# I2C_extender_1.net
KiCad netlist of a schematic drawn in Altium Designer
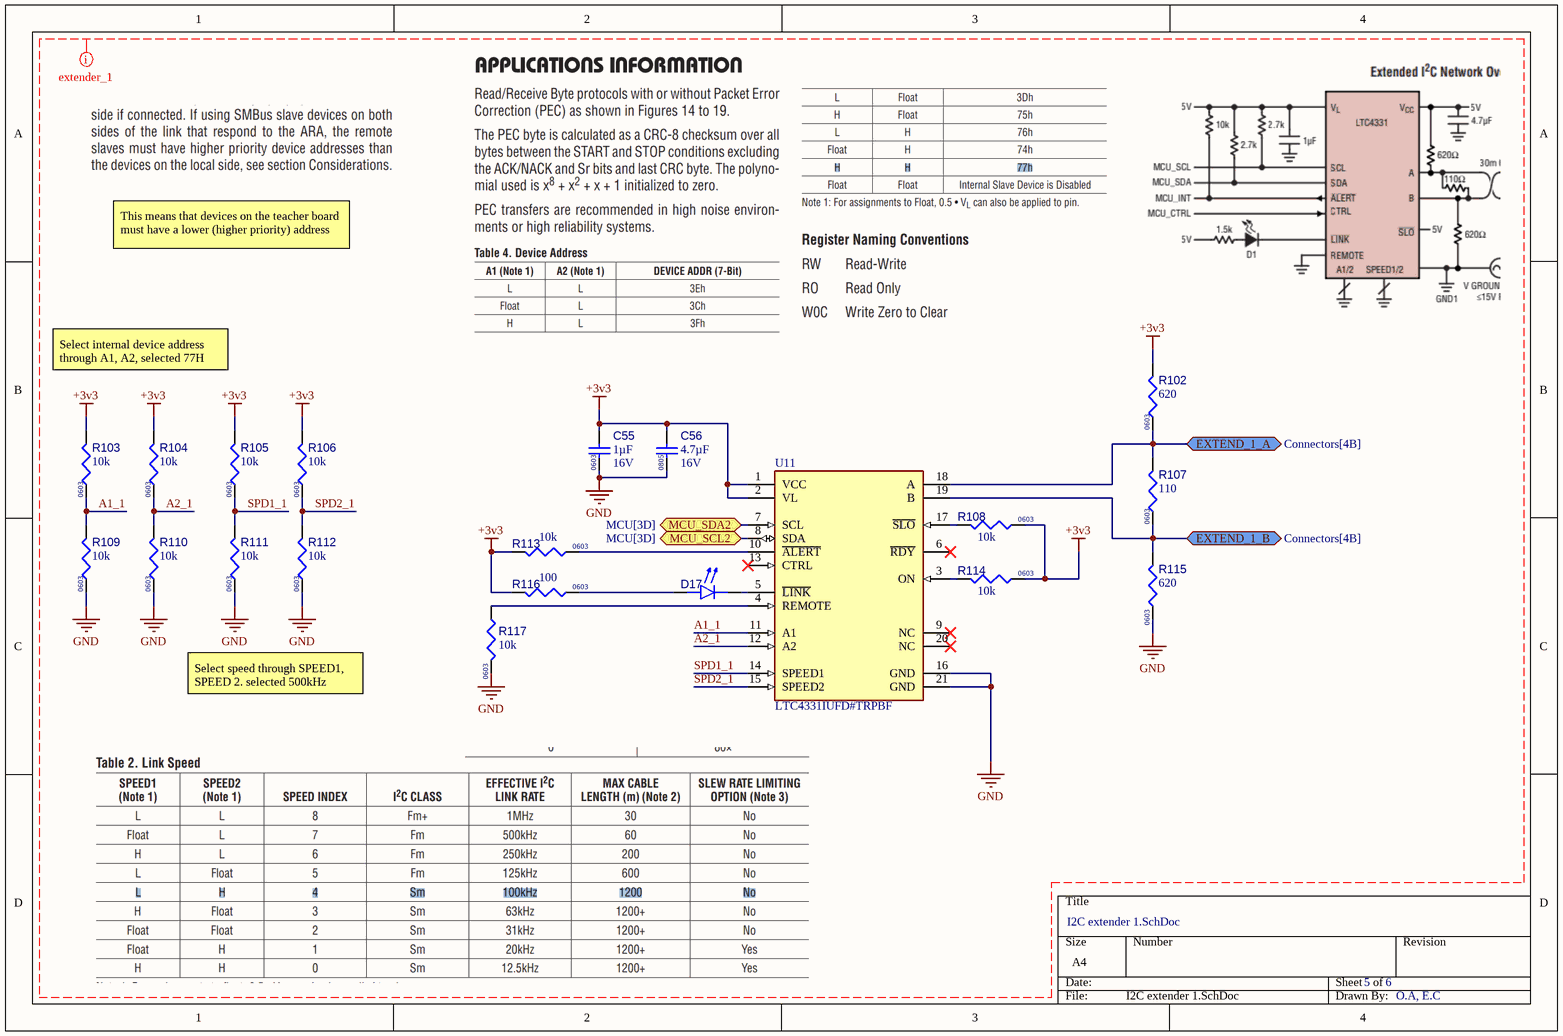
[diagram p0: I2C extender 1.SchDoc]

(export (version "E")
  (design (tool "Eeschema 10.0.6"))
  (components
    (comp (ref "C55")
      (value "1µF")
      (footprint "CAPC1608X90X35NL15T15")
      (description "Chip Capacitor, 1 uF, +/- 10%, 16 V, 0603 (1608 Metric)")
      (fields
        (field (name "CASE/PACKAGE") "0603")
        (field (name "VOLTAGE RATING") "16V")
        (field (name "TOLERANCE") "10%")
        (field (name "Comment") "Capacitor 1uF +/- 10% 16V 0603")
      )
      (libsource (lib "hawaiirobotics") (part "CAP-NP-2"))
    )
    (comp (ref "C56")
      (value "4.7µF")
      (footprint "CL21A475KOFNNNE-Footprint-1")
      (fields
        (field (name "CASE/PACKAGE") "0805")
        (field (name "RATED DC VOLTAGE (URDC)") "16V")
        (field (name "Comment") "CL21A475KOFNNNE")
      )
      (libsource (lib "hawaiirobotics") (part "CAP-NP-2"))
    )
    (comp (ref "D17")
      (value "150060YS75000")
      (footprint "WL-SMCW_0603_150060xx75000")
      (description "Single Color LED, Yellow, Water Clear, 1.1mm")
      (libsource (lib "hawaiirobotics") (part "DIODE-LED-2"))
    )
    (comp (ref "R102")
      (value "620")
      (footprint "RC0603JR-0720KL-Footprint-1")
      (fields
        (field (name "POWER") "100mW")
        (field (name "CASE/PACKAGE") "0603")
        (field (name "TOLERANCE") "1%")
        (field (name "Comment") "RC0603FR-07620RL")
      )
      (libsource (lib "hawaiirobotics") (part "RES-2"))
    )
    (comp (ref "R103")
      (value "10k")
      (footprint "RESC1608X55X25NL10T15")
      (description "Chip Resistor, 10 KOhm, +/- 1%, 01 W, -55 to 155 degC, 0603 (1608 Metric)")
      (fields
        (field (name "CASE/PACKAGE") "0603")
        (field (name "POWER") "100mW")
        (field (name "TOLERANCE") "1%")
      )
      (libsource (lib "hawaiirobotics") (part "RES-2"))
    )
    (comp (ref "R104")
      (value "10k")
      (footprint "RESC1608X55X25NL10T15")
      (description "Chip Resistor, 10 KOhm, +/- 1%, 01 W, -55 to 155 degC, 0603 (1608 Metric)")
      (fields
        (field (name "CASE/PACKAGE") "0603")
        (field (name "POWER") "100mW")
        (field (name "TOLERANCE") "1%")
      )
      (libsource (lib "hawaiirobotics") (part "RES-2"))
    )
    (comp (ref "R105")
      (value "10k")
      (footprint "RESC1608X55X25NL10T15")
      (description "Chip Resistor, 10 KOhm, +/- 1%, 01 W, -55 to 155 degC, 0603 (1608 Metric)")
      (fields
        (field (name "CASE/PACKAGE") "0603")
        (field (name "POWER") "100mW")
        (field (name "TOLERANCE") "1%")
      )
      (libsource (lib "hawaiirobotics") (part "RES-2"))
    )
    (comp (ref "R106")
      (value "10k")
      (footprint "RESC1608X55X25NL10T15")
      (description "Chip Resistor, 10 KOhm, +/- 1%, 01 W, -55 to 155 degC, 0603 (1608 Metric)")
      (fields
        (field (name "CASE/PACKAGE") "0603")
        (field (name "POWER") "100mW")
        (field (name "TOLERANCE") "1%")
      )
      (libsource (lib "hawaiirobotics") (part "RES-2"))
    )
    (comp (ref "R107")
      (value "110")
      (footprint "RC0603JR-0720KL-Footprint-1")
      (fields
        (field (name "TOLERANCE") "1%")
        (field (name "POWER") "100mW")
        (field (name "CASE/PACKAGE") "0603")
        (field (name "Comment") "RC0603FR-07110RL")
      )
      (libsource (lib "hawaiirobotics") (part "RES-2"))
    )
    (comp (ref "R108")
      (value "10k")
      (footprint "RESC1608X55X25NL10T15")
      (description "Chip Resistor, 10 KOhm, +/- 1%, 01 W, -55 to 155 degC, 0603 (1608 Metric)")
      (fields
        (field (name "CASE/PACKAGE") "0603")
        (field (name "POWER") "100mW")
        (field (name "TOLERANCE") "1%")
      )
      (libsource (lib "hawaiirobotics") (part "RES-2"))
    )
    (comp (ref "R109")
      (value "10k")
      (footprint "RESC1608X55X25NL10T15")
      (description "Chip Resistor, 10 KOhm, +/- 1%, 01 W, -55 to 155 degC, 0603 (1608 Metric)")
      (fields
        (field (name "CASE/PACKAGE") "0603")
        (field (name "POWER") "100mW")
        (field (name "TOLERANCE") "1%")
      )
      (libsource (lib "hawaiirobotics") (part "RES-2"))
    )
    (comp (ref "R110")
      (value "10k")
      (footprint "RESC1608X55X25NL10T15")
      (description "Chip Resistor, 10 KOhm, +/- 1%, 01 W, -55 to 155 degC, 0603 (1608 Metric)")
      (fields
        (field (name "CASE/PACKAGE") "0603")
        (field (name "POWER") "100mW")
        (field (name "TOLERANCE") "1%")
      )
      (libsource (lib "hawaiirobotics") (part "RES-2"))
    )
    (comp (ref "R111")
      (value "10k")
      (footprint "RESC1608X55X25NL10T15")
      (description "Chip Resistor, 10 KOhm, +/- 1%, 01 W, -55 to 155 degC, 0603 (1608 Metric)")
      (fields
        (field (name "CASE/PACKAGE") "0603")
        (field (name "POWER") "100mW")
        (field (name "TOLERANCE") "1%")
      )
      (libsource (lib "hawaiirobotics") (part "RES-2"))
    )
    (comp (ref "R112")
      (value "10k")
      (footprint "RESC1608X55X25NL10T15")
      (description "Chip Resistor, 10 KOhm, +/- 1%, 01 W, -55 to 155 degC, 0603 (1608 Metric)")
      (fields
        (field (name "CASE/PACKAGE") "0603")
        (field (name "POWER") "100mW")
        (field (name "TOLERANCE") "1%")
      )
      (libsource (lib "hawaiirobotics") (part "RES-2"))
    )
    (comp (ref "R113")
      (value "10k")
      (footprint "RESC1608X55X25NL10T15")
      (description "Chip Resistor, 10 KOhm, +/- 1%, 01 W, -55 to 155 degC, 0603 (1608 Metric)")
      (fields
        (field (name "CASE/PACKAGE") "0603")
        (field (name "POWER") "100mW")
        (field (name "TOLERANCE") "1%")
      )
      (libsource (lib "hawaiirobotics") (part "RES-2"))
    )
    (comp (ref "R114")
      (value "10k")
      (footprint "RESC1608X55X25NL10T15")
      (description "Chip Resistor, 10 KOhm, +/- 1%, 01 W, -55 to 155 degC, 0603 (1608 Metric)")
      (fields
        (field (name "CASE/PACKAGE") "0603")
        (field (name "POWER") "100mW")
        (field (name "TOLERANCE") "1%")
      )
      (libsource (lib "hawaiirobotics") (part "RES-2"))
    )
    (comp (ref "R115")
      (value "620")
      (footprint "RC0603JR-0720KL-Footprint-1")
      (fields
        (field (name "POWER") "100mW")
        (field (name "CASE/PACKAGE") "0603")
        (field (name "TOLERANCE") "1%")
        (field (name "Comment") "RC0603FR-07620RL")
      )
      (libsource (lib "hawaiirobotics") (part "RES-2"))
    )
    (comp (ref "R116")
      (value "100")
      (footprint "RC0603JR-0720KL-Footprint-1")
      (fields
        (field (name "TOLERANCE") "1%")
        (field (name "CASE/PACKAGE") "0603")
        (field (name "POWER") "100mW")
        (field (name "Comment") "RC0603FR-07100RL")
      )
      (libsource (lib "hawaiirobotics") (part "RES-2"))
    )
    (comp (ref "R117")
      (value "10k")
      (footprint "RESC1608X55X25NL10T15")
      (description "Chip Resistor, 10 KOhm, +/- 1%, 01 W, -55 to 155 degC, 0603 (1608 Metric)")
      (fields
        (field (name "CASE/PACKAGE") "0603")
        (field (name "POWER") "100mW")
        (field (name "TOLERANCE") "1%")
      )
      (libsource (lib "hawaiirobotics") (part "RES-2"))
    )
    (comp (ref "U11")
      (value "LTC4331IUFD#TRPBF")
      (footprint "FP-UFD-20-05-08-1711-IPC_C")
      (description "Interface Circuit, CMOS, PQCC20")
      (libsource (lib "hawaiirobotics") (part "90934f5fbb90c4d29cf3ee1665de234"))
    )
  )
  (nets
    (net (code "1") (name "+3v3") (class "Default")
      (node (ref "C55") (pin "2") (pinfunction "2_2") (pintype "passive"))
      (node (ref "C56") (pin "2") (pinfunction "2_2") (pintype "passive"))
      (node (ref "R102") (pin "2") (pinfunction "2_2") (pintype "passive"))
      (node (ref "R103") (pin "2") (pinfunction "2_2") (pintype "passive"))
      (node (ref "R104") (pin "2") (pinfunction "2_2") (pintype "passive"))
      (node (ref "R105") (pin "2") (pinfunction "2_2") (pintype "passive"))
      (node (ref "R106") (pin "2") (pinfunction "2_2") (pintype "passive"))
      (node (ref "R108") (pin "1") (pinfunction "1_1") (pintype "passive"))
      (node (ref "R113") (pin "1") (pinfunction "1_1") (pintype "passive"))
      (node (ref "R114") (pin "1") (pinfunction "1_1") (pintype "passive"))
      (node (ref "R116") (pin "2") (pinfunction "2_2") (pintype "passive"))
      (node (ref "U11") (pin "1") (pinfunction "VCC_1") (pintype "power_in"))
      (node (ref "U11") (pin "2") (pinfunction "VL_2") (pintype "power_in"))
    )
    (net (code "2") (name "/A1_1") (class "Default")
      (node (ref "R103") (pin "1") (pinfunction "1_1") (pintype "passive"))
      (node (ref "R109") (pin "2") (pinfunction "2_2") (pintype "passive"))
      (node (ref "U11") (pin "11") (pinfunction "A1_11") (pintype "input"))
    )
    (net (code "3") (name "/A2_1") (class "Default")
      (node (ref "R104") (pin "1") (pinfunction "1_1") (pintype "passive"))
      (node (ref "R110") (pin "2") (pinfunction "2_2") (pintype "passive"))
      (node (ref "U11") (pin "12") (pinfunction "A2_12") (pintype "input"))
    )
    (net (code "4") (name "/EXTEND_1_A") (class "Default")
      (node (ref "R102") (pin "1") (pinfunction "1_1") (pintype "passive"))
      (node (ref "R107") (pin "2") (pinfunction "2_2") (pintype "passive"))
      (node (ref "U11") (pin "18") (pinfunction "A_18") (pintype "tri_state"))
    )
    (net (code "5") (name "/EXTEND_1_B") (class "Default")
      (node (ref "R107") (pin "1") (pinfunction "1_1") (pintype "passive"))
      (node (ref "R115") (pin "2") (pinfunction "2_2") (pintype "passive"))
      (node (ref "U11") (pin "19") (pinfunction "B_19") (pintype "tri_state"))
    )
    (net (code "6") (name "/MCU_SCL2") (class "Default")
      (node (ref "U11") (pin "8") (pinfunction "SDA_8") (pintype "bidirectional"))
    )
    (net (code "7") (name "/MCU_SDA2") (class "Default")
      (node (ref "U11") (pin "7") (pinfunction "SCL_7") (pintype "input"))
    )
    (net (code "8") (name "/SPD1_1") (class "Default")
      (node (ref "R105") (pin "1") (pinfunction "1_1") (pintype "passive"))
      (node (ref "R111") (pin "2") (pinfunction "2_2") (pintype "passive"))
      (node (ref "U11") (pin "14") (pinfunction "SPEED1_14") (pintype "input"))
    )
    (net (code "9") (name "/SPD2_1") (class "Default")
      (node (ref "R106") (pin "1") (pinfunction "1_1") (pintype "passive"))
      (node (ref "R112") (pin "2") (pinfunction "2_2") (pintype "passive"))
      (node (ref "U11") (pin "15") (pinfunction "SPEED2_15") (pintype "input"))
    )
    (net (code "10") (name "GND") (class "Default")
      (node (ref "C55") (pin "1") (pinfunction "1_1") (pintype "passive"))
      (node (ref "C56") (pin "1") (pinfunction "1_1") (pintype "passive"))
      (node (ref "R109") (pin "1") (pinfunction "1_1") (pintype "passive"))
      (node (ref "R110") (pin "1") (pinfunction "1_1") (pintype "passive"))
      (node (ref "R111") (pin "1") (pinfunction "1_1") (pintype "passive"))
      (node (ref "R112") (pin "1") (pinfunction "1_1") (pintype "passive"))
      (node (ref "R115") (pin "1") (pinfunction "1_1") (pintype "passive"))
      (node (ref "R117") (pin "1") (pinfunction "1_1") (pintype "passive"))
      (node (ref "U11") (pin "16") (pinfunction "GND_16") (pintype "power_in"))
      (node (ref "U11") (pin "21") (pinfunction "GND_21") (pintype "power_in"))
    )
    (net (code "11") (name "Net-(D17-A)") (class "Default")
      (node (ref "D17") (pin "2") (pinfunction "A_2") (pintype "passive"))
      (node (ref "R116") (pin "1") (pinfunction "1_1") (pintype "passive"))
    )
    (net (code "12") (name "Net-(D17-K)") (class "Default")
      (node (ref "D17") (pin "1") (pinfunction "K_1") (pintype "passive"))
      (node (ref "U11") (pin "5") (pinfunction "~{LINK}_5") (pintype "open_collector"))
    )
    (net (code "13") (name "Net-(U11-ON)") (class "Default")
      (node (ref "R114") (pin "2") (pinfunction "2_2") (pintype "passive"))
      (node (ref "U11") (pin "3") (pinfunction "ON_3") (pintype "input"))
    )
    (net (code "14") (name "Net-(U11-REMOTE)") (class "Default")
      (node (ref "R117") (pin "2") (pinfunction "2_2") (pintype "passive"))
      (node (ref "U11") (pin "4") (pinfunction "REMOTE_4") (pintype "input"))
    )
    (net (code "15") (name "Net-(U11-~{ALERT})") (class "Default")
      (node (ref "R113") (pin "2") (pinfunction "2_2") (pintype "passive"))
      (node (ref "U11") (pin "10") (pinfunction "~{ALERT}_10") (pintype "open_collector"))
    )
    (net (code "16") (name "Net-(U11-~{SLO})") (class "Default")
      (node (ref "R108") (pin "2") (pinfunction "2_2") (pintype "passive"))
      (node (ref "U11") (pin "17") (pinfunction "~{SLO}_17") (pintype "input"))
    )
    (net (code "17") (name "unconnected-(U11-CTRL-Pad13)") (class "Default")
      (node (ref "U11") (pin "13") (pinfunction "CTRL_13") (pintype "input+no_connect"))
    )
    (net (code "18") (name "unconnected-(U11-NC-Pad9)") (class "Default")
      (node (ref "U11") (pin "9") (pinfunction "NC_9") (pintype "passive+no_connect"))
    )
    (net (code "19") (name "unconnected-(U11-NC-Pad20)") (class "Default")
      (node (ref "U11") (pin "20") (pinfunction "NC_20") (pintype "passive+no_connect"))
    )
    (net (code "20") (name "unconnected-(U11-~{RDY}-Pad6)") (class "Default")
      (node (ref "U11") (pin "6") (pinfunction "~{RDY}_6") (pintype "open_collector+no_connect"))
    )
  )
)
